# RubyWaves.net
KiCad netlist of a schematic drawn in EAGLE
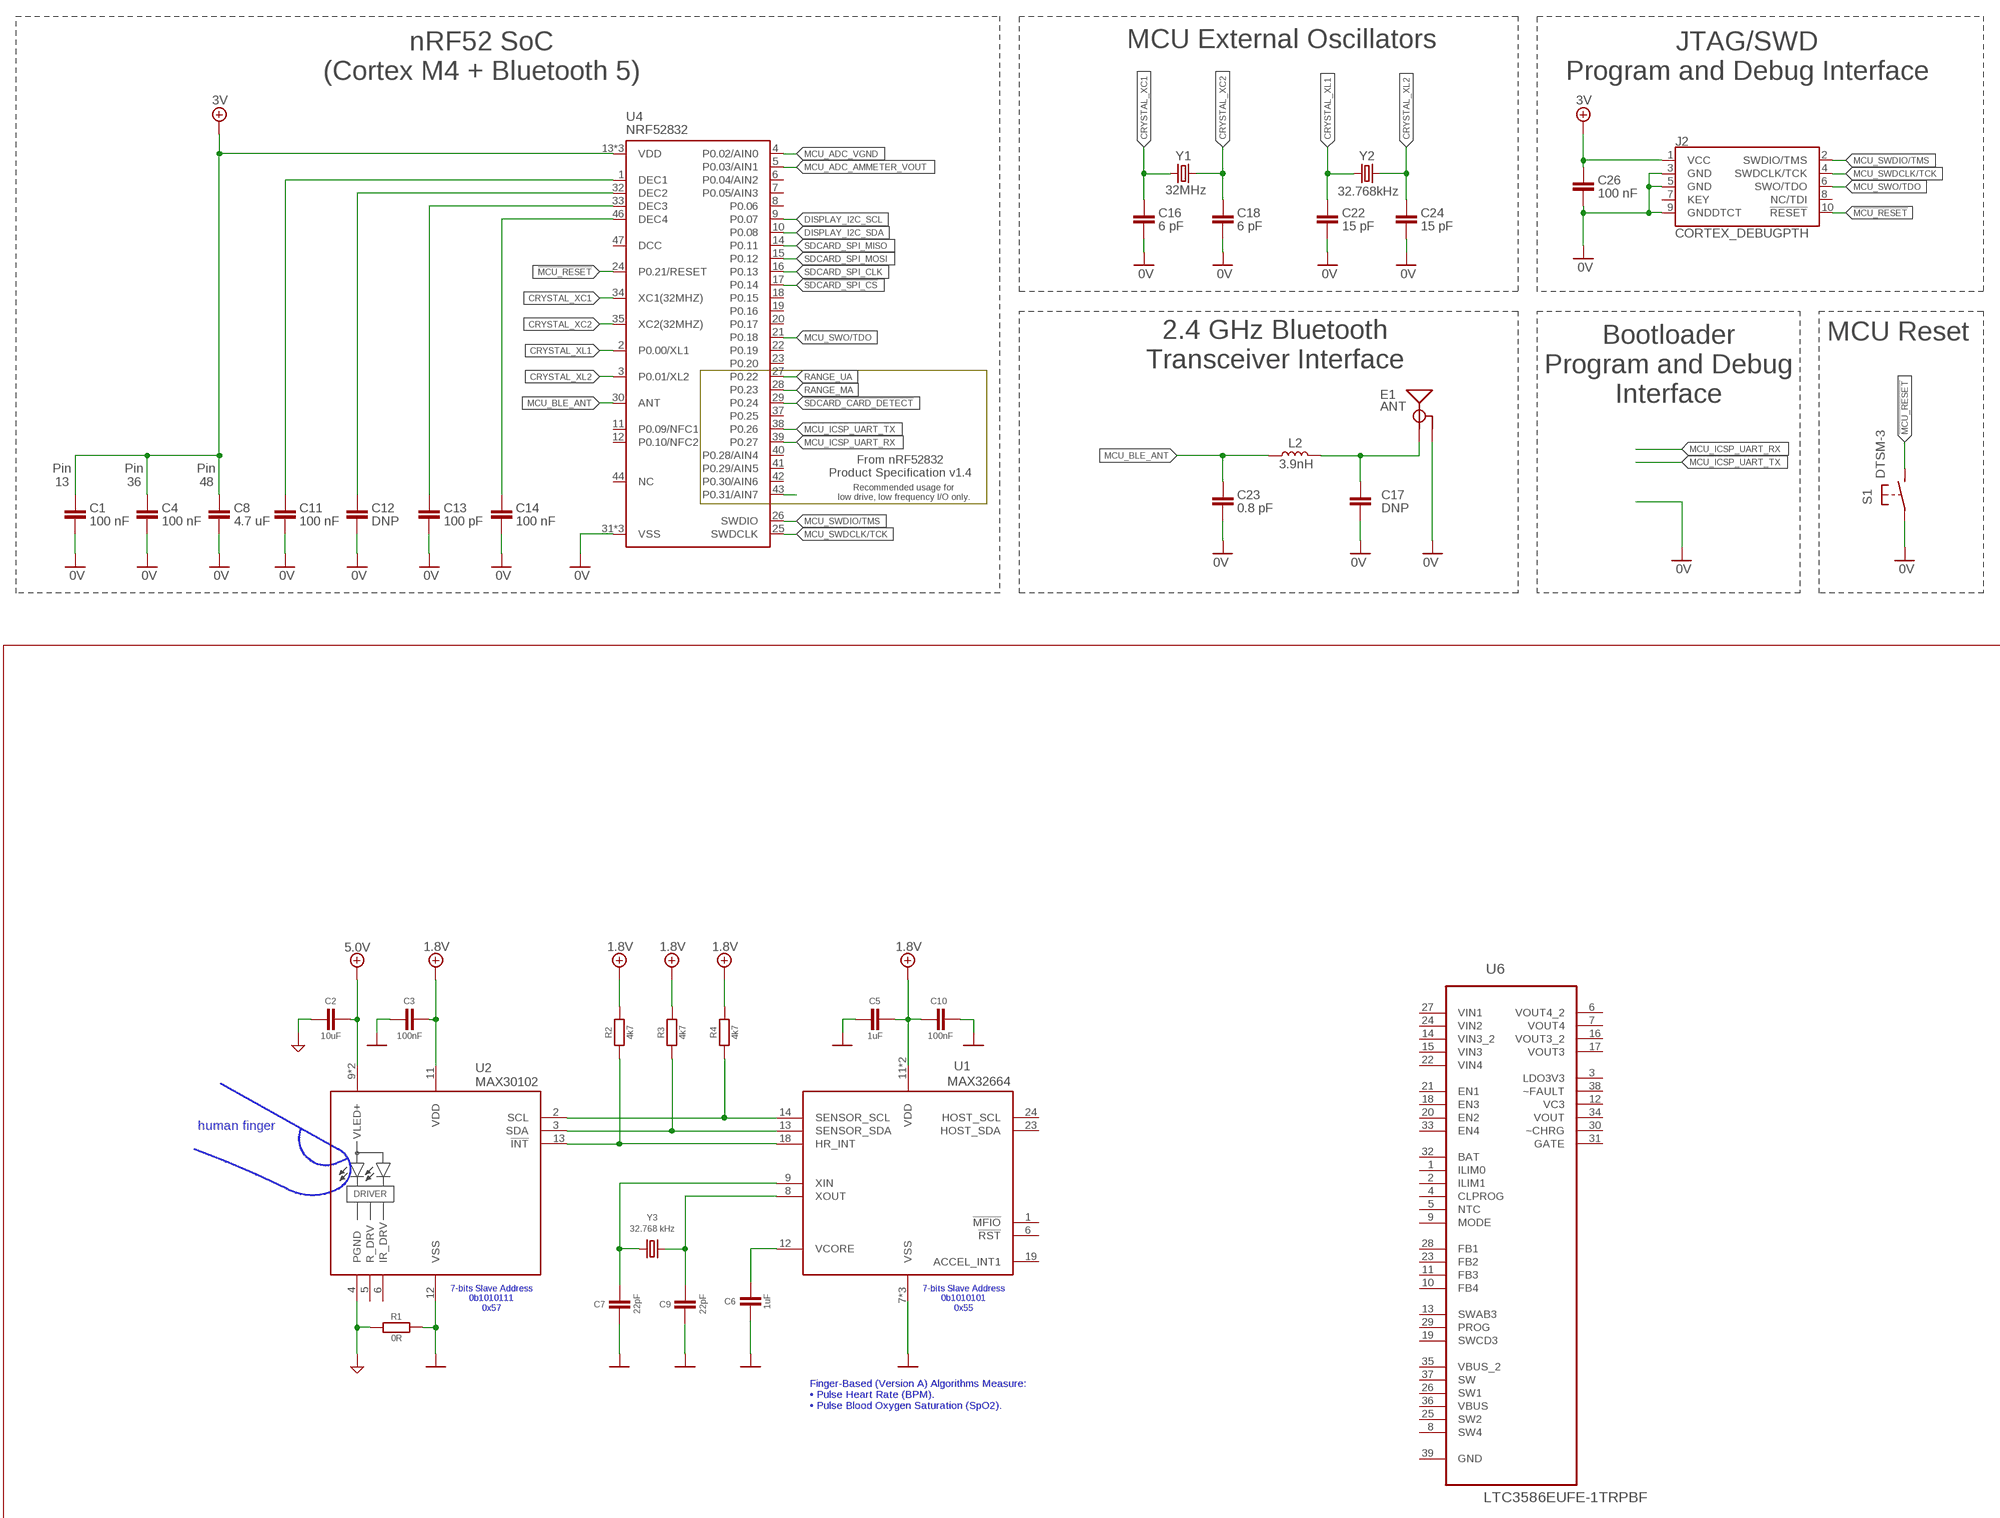
[diagram p0: schematic, sheet 1, part 1 of 2]
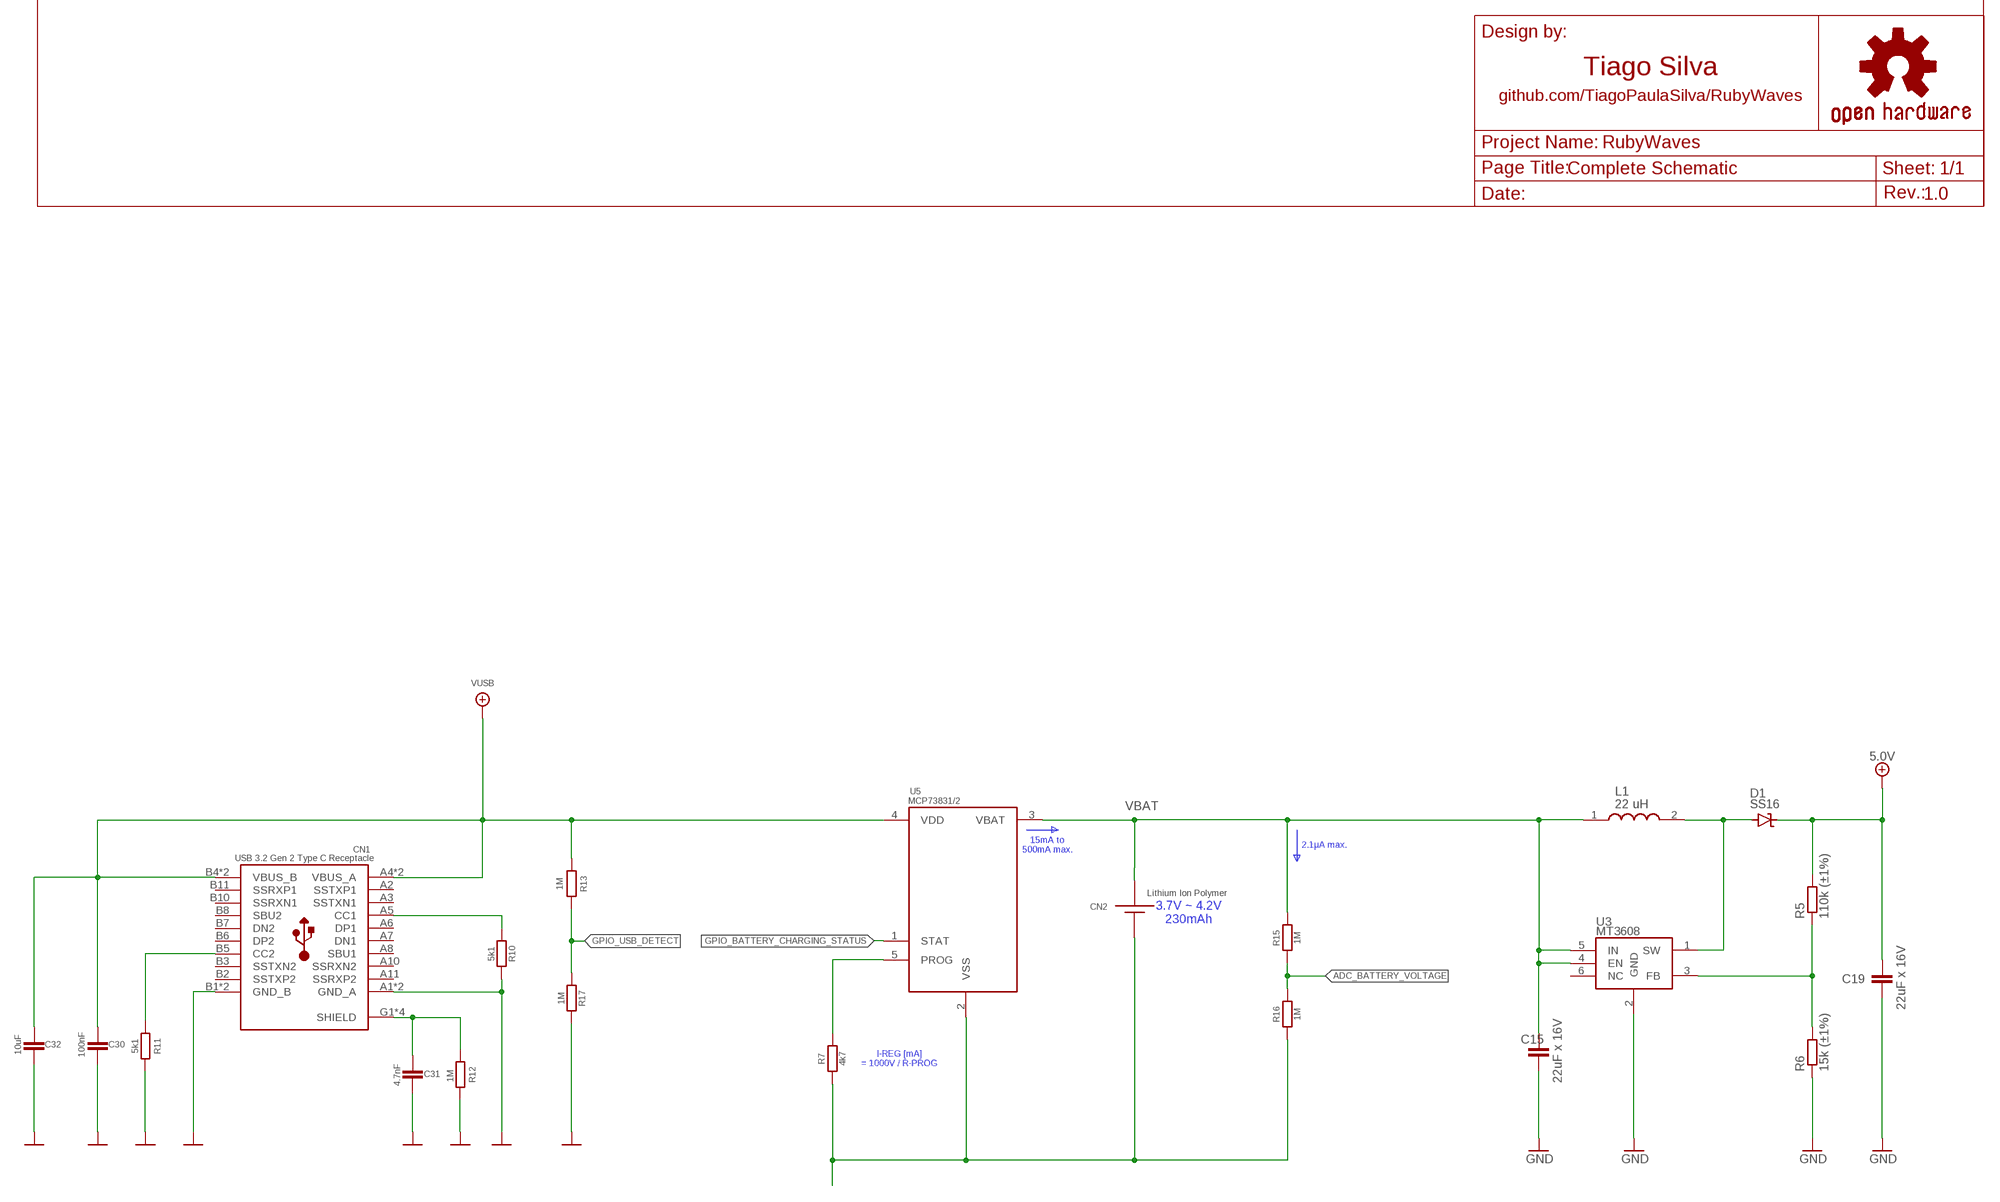
[diagram p1: schematic, sheet 1, part 2 of 2]

(export (version "E")
  (design (tool "Eeschema 10.0.6"))
  (components
    (comp (ref "C1")
      (value "100 nF")
      (footprint "eagle-import:C0603")
      (libsource (lib "eagle-import") (part "C-EUC0603"))
    )
    (comp (ref "C2")
      (value "10uF")
      (footprint "eagle-import:C0603")
      (libsource (lib "eagle-import") (part "C_0603"))
    )
    (comp (ref "C3")
      (value "100nF")
      (footprint "eagle-import:C0603")
      (libsource (lib "eagle-import") (part "C_0603"))
    )
    (comp (ref "C4")
      (value "100 nF")
      (footprint "eagle-import:C0603")
      (libsource (lib "eagle-import") (part "C-EUC0603"))
    )
    (comp (ref "C5")
      (value "1uF")
      (footprint "eagle-import:C0603")
      (libsource (lib "eagle-import") (part "C_0603"))
    )
    (comp (ref "C6")
      (value "1uF")
      (footprint "eagle-import:C0603")
      (libsource (lib "eagle-import") (part "C_0603"))
    )
    (comp (ref "C7")
      (value "22pF")
      (footprint "eagle-import:C0603")
      (libsource (lib "eagle-import") (part "C_0603"))
    )
    (comp (ref "C8")
      (value "4.7 uF")
      (footprint "eagle-import:C0603")
      (libsource (lib "eagle-import") (part "C-EUC0603"))
    )
    (comp (ref "C9")
      (value "22pF")
      (footprint "eagle-import:C0603")
      (libsource (lib "eagle-import") (part "C_0603"))
    )
    (comp (ref "C10")
      (value "100nF")
      (footprint "eagle-import:C0603")
      (libsource (lib "eagle-import") (part "C_0603"))
    )
    (comp (ref "C11")
      (value "100 nF")
      (footprint "eagle-import:C0603")
      (libsource (lib "eagle-import") (part "C-EUC0603"))
    )
    (comp (ref "C12")
      (value "DNP")
      (footprint "eagle-import:C0603")
      (libsource (lib "eagle-import") (part "C-EUC0603"))
    )
    (comp (ref "C13")
      (value "100 pF")
      (footprint "eagle-import:C0603")
      (libsource (lib "eagle-import") (part "C-EUC0603"))
    )
    (comp (ref "C14")
      (value "100 nF")
      (footprint "eagle-import:C0603")
      (libsource (lib "eagle-import") (part "C-EUC0603"))
    )
    (comp (ref "C15")
      (value "22uF x 16V")
      (footprint "eagle-import:C0805")
      (libsource (lib "eagle-import") (part "C-EUC0805"))
    )
    (comp (ref "C16")
      (value "6 pF")
      (footprint "eagle-import:C0603")
      (libsource (lib "eagle-import") (part "C-EUC0603"))
    )
    (comp (ref "C17")
      (value "DNP")
      (footprint "eagle-import:C0603")
      (libsource (lib "eagle-import") (part "C-EUC0603"))
    )
    (comp (ref "C18")
      (value "6 pF")
      (footprint "eagle-import:C0603")
      (libsource (lib "eagle-import") (part "C-EUC0603"))
    )
    (comp (ref "C19")
      (value "22uF x 16V")
      (footprint "eagle-import:C0805")
      (libsource (lib "eagle-import") (part "C-EUC0805"))
    )
    (comp (ref "C22")
      (value "15 pF")
      (footprint "eagle-import:C0603")
      (libsource (lib "eagle-import") (part "C-EUC0603"))
    )
    (comp (ref "C23")
      (value "0.8 pF")
      (footprint "eagle-import:C0603")
      (libsource (lib "eagle-import") (part "C-EUC0603"))
    )
    (comp (ref "C24")
      (value "15 pF")
      (footprint "eagle-import:C0603")
      (libsource (lib "eagle-import") (part "C-EUC0603"))
    )
    (comp (ref "C26")
      (value "100 nF")
      (footprint "eagle-import:C0603")
      (libsource (lib "eagle-import") (part "C-EUC0603"))
    )
    (comp (ref "C30")
      (value "100nF")
      (footprint "eagle-import:C0603")
      (libsource (lib "eagle-import") (part "C_0603"))
    )
    (comp (ref "C31")
      (value "4.7nF")
      (footprint "eagle-import:C0603")
      (libsource (lib "eagle-import") (part "C_0603"))
    )
    (comp (ref "C32")
      (value "10uF")
      (footprint "eagle-import:C0603")
      (libsource (lib "eagle-import") (part "C_0603"))
    )
    (comp (ref "CN1")
      (value "USB 3.2 Gen 2 Type C Receptacle")
      (footprint "eagle-import:GCT_USB4080-03-A_REVA")
      (fields (field (name "MF") "Global Connector Technology") (field (name "MP") "USB4080-03-A"))
      (libsource (lib "eagle-import") (part "USB4080-03-A"))
    )
    (comp (ref "CN2")
      (value "Lithium Ion Polymer")
      (footprint "eagle-import:JST-PH-2-SMT-RA")
      (libsource (lib "eagle-import") (part "BATTERYJST-2"))
    )
    (comp (ref "D1")
      (value "SS16")
      (footprint "eagle-import:SMBJ")
      (libsource (lib "eagle-import") (part "SUPPRESSOR-SMBJ"))
    )
    (comp (ref "E1")
      (value "ANT")
      (footprint "eagle-import:TRACE_ANTENNA_2.4GHZ_15.2MM")
      (libsource (lib "eagle-import") (part "ANTENNA-GROUNDEDTRACE-15.2MM"))
    )
    (comp (ref "J2")
      (value "CORTEX_DEBUGPTH")
      (footprint "eagle-import:2X5-PTH-1.27MM")
      (libsource (lib "eagle-import") (part "CORTEX_DEBUGPTH"))
    )
    (comp (ref "L1")
      (value "22 uH")
      (footprint "eagle-import:INDUCTOR")
      (libsource (lib "eagle-import") (part "INDUCTOR"))
    )
    (comp (ref "L2")
      (value "3.9nH")
      (footprint "eagle-import:0402")
      (libsource (lib "eagle-import") (part "INDUCTOR-0402-3.9NH"))
    )
    (comp (ref "R1")
      (value "0R")
      (footprint "eagle-import:R0603")
      (libsource (lib "eagle-import") (part "R_0603"))
    )
    (comp (ref "R2")
      (value "4k7")
      (footprint "eagle-import:R0603")
      (libsource (lib "eagle-import") (part "R_0603"))
    )
    (comp (ref "R3")
      (value "4k7")
      (footprint "eagle-import:R0603")
      (libsource (lib "eagle-import") (part "R_0603"))
    )
    (comp (ref "R4")
      (value "4k7")
      (footprint "eagle-import:R0603")
      (libsource (lib "eagle-import") (part "R_0603"))
    )
    (comp (ref "R5")
      (value "110k (±1%)")
      (footprint "eagle-import:R0603")
      (libsource (lib "eagle-import") (part "R-EU_R0603"))
    )
    (comp (ref "R6")
      (value "15k (±1%)")
      (footprint "eagle-import:R0603")
      (libsource (lib "eagle-import") (part "R-EU_R0603"))
    )
    (comp (ref "R7")
      (value "4k7")
      (footprint "eagle-import:R0603")
      (libsource (lib "eagle-import") (part "R_0603"))
    )
    (comp (ref "R10")
      (value "5k1")
      (footprint "eagle-import:R0603")
      (libsource (lib "eagle-import") (part "R_0603"))
    )
    (comp (ref "R11")
      (value "5k1")
      (footprint "eagle-import:R0603")
      (libsource (lib "eagle-import") (part "R_0603"))
    )
    (comp (ref "R12")
      (value "1M")
      (footprint "eagle-import:R0603")
      (libsource (lib "eagle-import") (part "R_0603"))
    )
    (comp (ref "R13")
      (value "1M")
      (footprint "eagle-import:R0603")
      (libsource (lib "eagle-import") (part "R_0603"))
    )
    (comp (ref "R15")
      (value "1M")
      (footprint "eagle-import:R0603")
      (libsource (lib "eagle-import") (part "R_0603"))
    )
    (comp (ref "R16")
      (value "1M")
      (footprint "eagle-import:R0603")
      (libsource (lib "eagle-import") (part "R_0603"))
    )
    (comp (ref "R17")
      (value "1M")
      (footprint "eagle-import:R0603")
      (libsource (lib "eagle-import") (part "R_0603"))
    )
    (comp (ref "S1")
      (value "DTSM-3")
      (footprint "eagle-import:SMD-2P")
      (libsource (lib "eagle-import") (part "DTSM-3"))
    )
    (comp (ref "U1")
      (value "MAX32664")
      (footprint "eagle-import:TQFN-24")
      (libsource (lib "eagle-import") (part "MAX32664"))
    )
    (comp (ref "U2")
      (value "MAX30102")
      (footprint "eagle-import:OESIP-14")
      (libsource (lib "eagle-import") (part "MAX30102"))
    )
    (comp (ref "U3")
      (value "MT3608")
      (footprint "eagle-import:SOT95P280X145-6N")
      (libsource (lib "eagle-import") (part "MT3608"))
    )
    (comp (ref "U4")
      (value "NRF52832")
      (footprint "eagle-import:QFN48-6X6MM")
      (libsource (lib "eagle-import") (part "NRF52832"))
    )
    (comp (ref "U5")
      (value "MCP73831/2")
      (footprint "eagle-import:SOT23-5L")
      (libsource (lib "eagle-import") (part "MCP73831/OT"))
    )
    (comp (ref "U6")
      (value "LTC3586EUFE-1TRPBF")
      (footprint "eagle-import:QFN40P400X600X80-39N")
      (fields (field (name "MF") "Analog Devices") (field (name "MP") "LTC3586EUFE-1#TRPBF"))
      (libsource (lib "eagle-import") (part "LTC3586EUFE-1TRPBF"))
    )
    (comp (ref "Y1")
      (value "32MHz")
      (footprint "eagle-import:CRYSTAL-SMD-2.0X1.6MM")
      (libsource (lib "eagle-import") (part "CRYSTAL-32MHZ-SMD-2.0X1.6MM"))
    )
    (comp (ref "Y2")
      (value "32.768kHz")
      (footprint "eagle-import:CRYSTAL-SMD-3.2X1.5MM")
      (libsource (lib "eagle-import") (part "CRYSTAL-32.768KHZSMD-3.2X1.5"))
    )
    (comp (ref "Y3")
      (value "32.768 kHz")
      (footprint "eagle-import:3.2X1.5")
      (libsource (lib "eagle-import") (part "CRYSTAL-MINI"))
    )
  )
  (nets
    (net (code "1") (name "/VBAT") (class "Default")
      (node (ref "C15") (pin "1") (pinfunction "1_1") (pintype "passive"))
      (node (ref "CN2") (pin "1") (pinfunction "VDD_1") (pintype "power_in"))
      (node (ref "L1") (pin "1") (pinfunction "1_1") (pintype "bidirectional"))
      (node (ref "R15") (pin "2") (pinfunction "2_2") (pintype "passive"))
      (node (ref "U3") (pin "4") (pinfunction "EN_4") (pintype "bidirectional"))
      (node (ref "U3") (pin "5") (pinfunction "IN_5") (pintype "bidirectional"))
      (node (ref "U5") (pin "3") (pinfunction "VBAT_3") (pintype "bidirectional"))
    )
    (net (code "2") (name "/VBUS") (class "Default")
      (node (ref "U6") (pin "36") (pinfunction "VBUS_36") (pintype "power_in"))
    )
    (net (code "3") (name "/VBUS_2") (class "Default")
      (node (ref "U6") (pin "35") (pinfunction "VBUS_2_35") (pintype "power_in"))
    )
    (net (code "4") (name "/VIN1") (class "Default")
      (node (ref "U6") (pin "27") (pinfunction "VIN1_27") (pintype "power_in"))
    )
    (net (code "5") (name "/VIN2") (class "Default")
      (node (ref "U6") (pin "24") (pinfunction "VIN2_24") (pintype "power_in"))
    )
    (net (code "6") (name "/VIN3") (class "Default")
      (node (ref "U6") (pin "15") (pinfunction "VIN3_15") (pintype "power_in"))
    )
    (net (code "7") (name "/VIN3_2") (class "Default")
      (node (ref "U6") (pin "14") (pinfunction "VIN3_2_14") (pintype "power_in"))
    )
    (net (code "8") (name "/VIN4") (class "Default")
      (node (ref "U6") (pin "22") (pinfunction "VIN4_22") (pintype "power_in"))
    )
    (net (code "9") (name "/~{MCU_RESET}") (class "Default")
      (node (ref "J2") (pin "10") (pinfunction "~{RESET}_10") (pintype "bidirectional"))
      (node (ref "S1") (pin "2") (pinfunction "2_2") (pintype "passive"))
      (node (ref "U4") (pin "24") (pinfunction "P0.21/RESET_24") (pintype "bidirectional"))
    )
    (net (code "10") (name "/~{SDCARD_CARD_DETECT}") (class "Default")
      (node (ref "U4") (pin "29") (pinfunction "P0.24_29") (pintype "bidirectional"))
    )
    (net (code "11") (name "/~{SDCARD_SPI_CS}") (class "Default")
      (node (ref "U4") (pin "17") (pinfunction "P0.14_17") (pintype "bidirectional"))
    )
    (net (code "12") (name "0V") (class "Default")
      (node (ref "C1") (pin "2") (pinfunction "2_2") (pintype "passive"))
      (node (ref "C11") (pin "2") (pinfunction "2_2") (pintype "passive"))
      (node (ref "C12") (pin "2") (pinfunction "2_2") (pintype "passive"))
      (node (ref "C13") (pin "2") (pinfunction "2_2") (pintype "passive"))
      (node (ref "C14") (pin "2") (pinfunction "2_2") (pintype "passive"))
      (node (ref "C16") (pin "2") (pinfunction "2_2") (pintype "passive"))
      (node (ref "C17") (pin "2") (pinfunction "2_2") (pintype "passive"))
      (node (ref "C18") (pin "2") (pinfunction "2_2") (pintype "passive"))
      (node (ref "C22") (pin "2") (pinfunction "2_2") (pintype "passive"))
      (node (ref "C23") (pin "2") (pinfunction "2_2") (pintype "passive"))
      (node (ref "C24") (pin "2") (pinfunction "2_2") (pintype "passive"))
      (node (ref "C26") (pin "2") (pinfunction "2_2") (pintype "passive"))
      (node (ref "C30") (pin "1") (pinfunction "1_1") (pintype "passive"))
      (node (ref "C31") (pin "1") (pinfunction "1_1") (pintype "passive"))
      (node (ref "C32") (pin "1") (pinfunction "1_1") (pintype "passive"))
      (node (ref "C4") (pin "2") (pinfunction "2_2") (pintype "passive"))
      (node (ref "C8") (pin "2") (pinfunction "2_2") (pintype "passive"))
      (node (ref "CN1") (pin "A1") (pinfunction "GND_A_A1") (pintype "power_in"))
      (node (ref "CN1") (pin "A12") (pinfunction "GND_A_A12") (pintype "power_in"))
      (node (ref "CN1") (pin "B1") (pinfunction "GND_B_B1") (pintype "power_in"))
      (node (ref "CN1") (pin "B12") (pinfunction "GND_B_B12") (pintype "power_in"))
      (node (ref "E1") (pin "GND") (pinfunction "GND_GND") (pintype "bidirectional"))
      (node (ref "J2") (pin "3") (pinfunction "GND_3") (pintype "bidirectional"))
      (node (ref "J2") (pin "5") (pinfunction "GND_5") (pintype "bidirectional"))
      (node (ref "J2") (pin "9") (pinfunction "GNDDTCT_9") (pintype "bidirectional"))
      (node (ref "R10") (pin "2") (pinfunction "2_2") (pintype "passive"))
      (node (ref "R11") (pin "2") (pinfunction "2_2") (pintype "passive"))
      (node (ref "R12") (pin "2") (pinfunction "2_2") (pintype "passive"))
      (node (ref "R17") (pin "1") (pinfunction "1_1") (pintype "passive"))
      (node (ref "S1") (pin "1") (pinfunction "1_1") (pintype "passive"))
      (node (ref "U4") (pin "31") (pinfunction "VSS_31") (pintype "bidirectional"))
      (node (ref "U4") (pin "45") (pinfunction "VSS_45") (pintype "bidirectional"))
      (node (ref "U4") (pin "EP") (pinfunction "VSS_EP") (pintype "bidirectional"))
    )
    (net (code "13") (name "1.8V") (class "Default")
      (node (ref "C10") (pin "1") (pinfunction "1_1") (pintype "passive"))
      (node (ref "C3") (pin "1") (pinfunction "1_1") (pintype "passive"))
      (node (ref "C5") (pin "1") (pinfunction "1_1") (pintype "passive"))
      (node (ref "R2") (pin "2") (pinfunction "2_2") (pintype "passive"))
      (node (ref "R3") (pin "2") (pinfunction "2_2") (pintype "passive"))
      (node (ref "R4") (pin "2") (pinfunction "2_2") (pintype "passive"))
      (node (ref "U1") (pin "11") (pinfunction "VDD_11") (pintype "bidirectional"))
      (node (ref "U1") (pin "22") (pinfunction "VDD_22") (pintype "bidirectional"))
      (node (ref "U2") (pin "11") (pinfunction "VDD_11") (pintype "power_in"))
    )
    (net (code "14") (name "3V") (class "Default")
      (node (ref "C1") (pin "1") (pinfunction "1_1") (pintype "passive"))
      (node (ref "C26") (pin "1") (pinfunction "1_1") (pintype "passive"))
      (node (ref "C4") (pin "1") (pinfunction "1_1") (pintype "passive"))
      (node (ref "C8") (pin "1") (pinfunction "1_1") (pintype "passive"))
      (node (ref "J2") (pin "1") (pinfunction "VCC_1") (pintype "bidirectional"))
      (node (ref "U4") (pin "13") (pinfunction "VDD_13") (pintype "bidirectional"))
      (node (ref "U4") (pin "36") (pinfunction "VDD_36") (pintype "bidirectional"))
      (node (ref "U4") (pin "48") (pinfunction "VDD_48") (pintype "bidirectional"))
    )
    (net (code "15") (name "5.0V") (class "Default")
      (node (ref "C19") (pin "1") (pinfunction "1_1") (pintype "passive"))
      (node (ref "C2") (pin "1") (pinfunction "1_1") (pintype "passive"))
      (node (ref "D1") (pin "C") (pinfunction "C_C") (pintype "passive"))
      (node (ref "R5") (pin "2") (pinfunction "2_2") (pintype "passive"))
      (node (ref "U2") (pin "10") (pinfunction "VLED+_10") (pintype "power_in"))
      (node (ref "U2") (pin "9") (pinfunction "VLED+_9") (pintype "power_in"))
    )
    (net (code "16") (name "ADC_BATTERY_VOLTAGE") (class "Default")
      (node (ref "R15") (pin "1") (pinfunction "1_1") (pintype "passive"))
      (node (ref "R16") (pin "2") (pinfunction "2_2") (pintype "passive"))
    )
    (net (code "17") (name "CRYSTAL_XC1") (class "Default")
      (node (ref "C16") (pin "1") (pinfunction "1_1") (pintype "passive"))
      (node (ref "U4") (pin "34") (pinfunction "XC1(32MHZ)_34") (pintype "bidirectional"))
      (node (ref "Y1") (pin "3") (pinfunction "2_3") (pintype "passive"))
    )
    (net (code "18") (name "CRYSTAL_XC2") (class "Default")
      (node (ref "C18") (pin "1") (pinfunction "1_1") (pintype "passive"))
      (node (ref "U4") (pin "35") (pinfunction "XC2(32MHZ)_35") (pintype "bidirectional"))
      (node (ref "Y1") (pin "1") (pinfunction "1_1") (pintype "passive"))
    )
    (net (code "19") (name "CRYSTAL_XL1") (class "Default")
      (node (ref "C22") (pin "1") (pinfunction "1_1") (pintype "passive"))
      (node (ref "U4") (pin "2") (pinfunction "P0.00/XL1_2") (pintype "bidirectional"))
      (node (ref "Y2") (pin "P$2") (pinfunction "2_P$2") (pintype "passive"))
    )
    (net (code "20") (name "CRYSTAL_XL2") (class "Default")
      (node (ref "C24") (pin "1") (pinfunction "1_1") (pintype "passive"))
      (node (ref "U4") (pin "3") (pinfunction "P0.01/XL2_3") (pintype "bidirectional"))
      (node (ref "Y2") (pin "P$1") (pinfunction "1_P$1") (pintype "passive"))
    )
    (net (code "21") (name "DGND") (class "Default")
      (node (ref "C2") (pin "2") (pinfunction "2_2") (pintype "passive"))
      (node (ref "R1") (pin "1") (pinfunction "1_1") (pintype "passive"))
      (node (ref "U2") (pin "4") (pinfunction "PGND_4") (pintype "power_in"))
    )
    (net (code "22") (name "DISPLAY_I2C_SCL") (class "Default")
      (node (ref "U4") (pin "9") (pinfunction "P0.07_9") (pintype "bidirectional"))
    )
    (net (code "23") (name "DISPLAY_I2C_SDA") (class "Default")
      (node (ref "U4") (pin "10") (pinfunction "P0.08_10") (pintype "bidirectional"))
    )
    (net (code "24") (name "GND") (class "Default")
      (node (ref "C15") (pin "2") (pinfunction "2_2") (pintype "passive"))
      (node (ref "C19") (pin "2") (pinfunction "2_2") (pintype "passive"))
      (node (ref "R6") (pin "1") (pinfunction "1_1") (pintype "passive"))
      (node (ref "U3") (pin "2") (pinfunction "GND_2") (pintype "bidirectional"))
    )
    (net (code "25") (name "GPIO_BATTERY_CHARGING_STATUS") (class "Default")
      (node (ref "U5") (pin "1") (pinfunction "STAT_1") (pintype "output"))
    )
    (net (code "26") (name "GPIO_USB_DETECT") (class "Default")
      (node (ref "R13") (pin "1") (pinfunction "1_1") (pintype "passive"))
      (node (ref "R17") (pin "2") (pinfunction "2_2") (pintype "passive"))
    )
    (net (code "27") (name "MCU_ADC_AMMETER_VOUT") (class "Default")
      (node (ref "U4") (pin "5") (pinfunction "P0.03/AIN1_5") (pintype "bidirectional"))
    )
    (net (code "28") (name "MCU_ADC_VGND") (class "Default")
      (node (ref "U4") (pin "4") (pinfunction "P0.02/AIN0_4") (pintype "bidirectional"))
    )
    (net (code "29") (name "MCU_BLE_ANT") (class "Default")
      (node (ref "C23") (pin "1") (pinfunction "1_1") (pintype "passive"))
      (node (ref "L2") (pin "2") (pinfunction "2_2") (pintype "passive"))
      (node (ref "U4") (pin "30") (pinfunction "ANT_30") (pintype "bidirectional"))
    )
    (net (code "30") (name "MCU_ICSP_UART_RX") (class "Default")
      (node (ref "U4") (pin "39") (pinfunction "P0.27_39") (pintype "bidirectional"))
    )
    (net (code "31") (name "MCU_ICSP_UART_TX") (class "Default")
      (node (ref "U4") (pin "38") (pinfunction "P0.26_38") (pintype "bidirectional"))
    )
    (net (code "32") (name "MCU_SWDCLK{slash}TCK") (class "Default")
      (node (ref "J2") (pin "4") (pinfunction "SWDCLK/TCK_4") (pintype "bidirectional"))
      (node (ref "U4") (pin "25") (pinfunction "SWDCLK_25") (pintype "bidirectional"))
    )
    (net (code "33") (name "MCU_SWDIO{slash}TMS") (class "Default")
      (node (ref "J2") (pin "2") (pinfunction "SWDIO/TMS_2") (pintype "bidirectional"))
      (node (ref "U4") (pin "26") (pinfunction "SWDIO_26") (pintype "bidirectional"))
    )
    (net (code "34") (name "MCU_SWO{slash}TDO") (class "Default")
      (node (ref "J2") (pin "6") (pinfunction "SWO/TDO_6") (pintype "bidirectional"))
      (node (ref "U4") (pin "21") (pinfunction "P0.18_21") (pintype "bidirectional"))
    )
    (net (code "35") (name "Net-(C31-Pad2)") (class "Default")
      (node (ref "C31") (pin "2") (pinfunction "2_2") (pintype "passive"))
      (node (ref "CN1") (pin "G1") (pinfunction "SHIELD_G1") (pintype "passive"))
      (node (ref "CN1") (pin "G2") (pinfunction "SHIELD_G2") (pintype "passive"))
      (node (ref "CN1") (pin "G3") (pinfunction "SHIELD_G3") (pintype "passive"))
      (node (ref "CN1") (pin "G4") (pinfunction "SHIELD_G4") (pintype "passive"))
      (node (ref "R12") (pin "1") (pinfunction "1_1") (pintype "passive"))
    )
    (net (code "36") (name "Net-(CN1-CC1)") (class "Default")
      (node (ref "CN1") (pin "A5") (pinfunction "CC1_A5") (pintype "bidirectional"))
      (node (ref "R10") (pin "1") (pinfunction "1_1") (pintype "passive"))
    )
    (net (code "37") (name "Net-(CN1-CC2)") (class "Default")
      (node (ref "CN1") (pin "B5") (pinfunction "CC2_B5") (pintype "bidirectional"))
      (node (ref "R11") (pin "1") (pinfunction "1_1") (pintype "passive"))
    )
    (net (code "38") (name "Net-(CN2-GND)") (class "Default")
      (node (ref "CN2") (pin "2") (pinfunction "GND_2") (pintype "power_in"))
      (node (ref "R16") (pin "1") (pinfunction "1_1") (pintype "passive"))
      (node (ref "R7") (pin "1") (pinfunction "1_1") (pintype "passive"))
      (node (ref "U5") (pin "2") (pinfunction "VSS_2") (pintype "power_in"))
    )
    (net (code "39") (name "Net-(E1-SIGNAL)") (class "Default")
      (node (ref "C17") (pin "1") (pinfunction "1_1") (pintype "passive"))
      (node (ref "E1") (pin "ANT") (pinfunction "SIGNAL_ANT") (pintype "bidirectional"))
      (node (ref "L2") (pin "1") (pinfunction "1_1") (pintype "passive"))
    )
    (net (code "40") (name "Net-(U1-HR_INT)") (class "Default")
      (node (ref "R2") (pin "1") (pinfunction "1_1") (pintype "passive"))
      (node (ref "U1") (pin "18") (pinfunction "HR_INT_18") (pintype "bidirectional"))
      (node (ref "U2") (pin "13") (pinfunction "~{INT}_13") (pintype "output"))
    )
    (net (code "41") (name "Net-(U1-SENSOR_SCL)") (class "Default")
      (node (ref "R4") (pin "1") (pinfunction "1_1") (pintype "passive"))
      (node (ref "U1") (pin "14") (pinfunction "SENSOR_SCL_14") (pintype "bidirectional"))
      (node (ref "U2") (pin "2") (pinfunction "SCL_2") (pintype "bidirectional"))
    )
    (net (code "42") (name "Net-(U1-SENSOR_SDA)") (class "Default")
      (node (ref "R3") (pin "1") (pinfunction "1_1") (pintype "passive"))
      (node (ref "U1") (pin "13") (pinfunction "SENSOR_SDA_13") (pintype "bidirectional"))
      (node (ref "U2") (pin "3") (pinfunction "SDA_3") (pintype "bidirectional"))
    )
    (net (code "43") (name "Net-(U1-VCORE)") (class "Default")
      (node (ref "C6") (pin "1") (pinfunction "1_1") (pintype "passive"))
      (node (ref "U1") (pin "12") (pinfunction "VCORE_12") (pintype "bidirectional"))
    )
    (net (code "44") (name "Net-(U1-XIN)") (class "Default")
      (node (ref "C7") (pin "1") (pinfunction "1_1") (pintype "passive"))
      (node (ref "U1") (pin "9") (pinfunction "XIN_9") (pintype "bidirectional"))
      (node (ref "Y3") (pin "1") (pinfunction "1_1") (pintype "passive"))
    )
    (net (code "45") (name "Net-(U1-XOUT)") (class "Default")
      (node (ref "C9") (pin "1") (pinfunction "1_1") (pintype "passive"))
      (node (ref "U1") (pin "8") (pinfunction "XOUT_8") (pintype "bidirectional"))
      (node (ref "Y3") (pin "2") (pinfunction "2_2") (pintype "passive"))
    )
    (net (code "46") (name "Net-(U3-FB)") (class "Default")
      (node (ref "R5") (pin "1") (pinfunction "1_1") (pintype "passive"))
      (node (ref "R6") (pin "2") (pinfunction "2_2") (pintype "passive"))
      (node (ref "U3") (pin "3") (pinfunction "FB_3") (pintype "bidirectional"))
    )
    (net (code "47") (name "Net-(U3-SW)") (class "Default")
      (node (ref "D1") (pin "A") (pinfunction "A_A") (pintype "passive"))
      (node (ref "L1") (pin "2") (pinfunction "2_2") (pintype "bidirectional"))
      (node (ref "U3") (pin "1") (pinfunction "SW_1") (pintype "bidirectional"))
    )
    (net (code "48") (name "Net-(U4-DEC1)") (class "Default")
      (node (ref "C11") (pin "1") (pinfunction "1_1") (pintype "passive"))
      (node (ref "U4") (pin "1") (pinfunction "DEC1_1") (pintype "bidirectional"))
    )
    (net (code "49") (name "Net-(U4-DEC2)") (class "Default")
      (node (ref "C12") (pin "1") (pinfunction "1_1") (pintype "passive"))
      (node (ref "U4") (pin "32") (pinfunction "DEC2_32") (pintype "bidirectional"))
    )
    (net (code "50") (name "Net-(U4-DEC3)") (class "Default")
      (node (ref "C13") (pin "1") (pinfunction "1_1") (pintype "passive"))
      (node (ref "U4") (pin "33") (pinfunction "DEC3_33") (pintype "bidirectional"))
    )
    (net (code "51") (name "Net-(U4-DEC4)") (class "Default")
      (node (ref "C14") (pin "1") (pinfunction "1_1") (pintype "passive"))
      (node (ref "U4") (pin "46") (pinfunction "DEC4_46") (pintype "bidirectional"))
    )
    (net (code "52") (name "Net-(U5-PROG)") (class "Default")
      (node (ref "R7") (pin "2") (pinfunction "2_2") (pintype "passive"))
      (node (ref "U5") (pin "5") (pinfunction "PROG_5") (pintype "input"))
    )
    (net (code "53") (name "RANGE_MA") (class "Default")
      (node (ref "U4") (pin "28") (pinfunction "P0.23_28") (pintype "bidirectional"))
    )
    (net (code "54") (name "RANGE_UA") (class "Default")
      (node (ref "U4") (pin "27") (pinfunction "P0.22_27") (pintype "bidirectional"))
    )
    (net (code "55") (name "SDCARD_SPI_CLK") (class "Default")
      (node (ref "U4") (pin "16") (pinfunction "P0.13_16") (pintype "bidirectional"))
    )
    (net (code "56") (name "SDCARD_SPI_MISO") (class "Default")
      (node (ref "U4") (pin "14") (pinfunction "P0.11_14") (pintype "bidirectional"))
    )
    (net (code "57") (name "SDCARD_SPI_MOSI") (class "Default")
      (node (ref "U4") (pin "15") (pinfunction "P0.12_15") (pintype "bidirectional"))
    )
    (net (code "58") (name "VSS") (class "Default")
      (node (ref "C10") (pin "2") (pinfunction "2_2") (pintype "passive"))
      (node (ref "C3") (pin "2") (pinfunction "2_2") (pintype "passive"))
      (node (ref "C5") (pin "2") (pinfunction "2_2") (pintype "passive"))
      (node (ref "C6") (pin "2") (pinfunction "2_2") (pintype "passive"))
      (node (ref "C7") (pin "2") (pinfunction "2_2") (pintype "passive"))
      (node (ref "C9") (pin "2") (pinfunction "2_2") (pintype "passive"))
      (node (ref "R1") (pin "2") (pinfunction "2_2") (pintype "passive"))
      (node (ref "U1") (pin "10") (pinfunction "VSS_10") (pintype "bidirectional"))
      (node (ref "U1") (pin "7") (pinfunction "VSS_7") (pintype "bidirectional"))
      (node (ref "U1") (pin "EP") (pinfunction "VSS_EP") (pintype "bidirectional"))
      (node (ref "U2") (pin "12") (pinfunction "VSS_12") (pintype "power_in"))
    )
    (net (code "59") (name "VUSB") (class "Default")
      (node (ref "C30") (pin "2") (pinfunction "2_2") (pintype "passive"))
      (node (ref "C32") (pin "2") (pinfunction "2_2") (pintype "passive"))
      (node (ref "CN1") (pin "A4") (pinfunction "VBUS_A_A4") (pintype "power_in"))
      (node (ref "CN1") (pin "A9") (pinfunction "VBUS_A_A9") (pintype "power_in"))
      (node (ref "CN1") (pin "B4") (pinfunction "VBUS_B_B4") (pintype "power_in"))
      (node (ref "CN1") (pin "B9") (pinfunction "VBUS_B_B9") (pintype "power_in"))
      (node (ref "R13") (pin "2") (pinfunction "2_2") (pintype "passive"))
      (node (ref "U5") (pin "4") (pinfunction "VDD_4") (pintype "power_in"))
    )
    (net (code "60") (name "unconnected-(CN1-DN1-PadA7)") (class "Default")
      (node (ref "CN1") (pin "A7") (pinfunction "DN1_A7") (pintype "bidirectional"))
    )
    (net (code "61") (name "unconnected-(CN1-DN2-PadB7)") (class "Default")
      (node (ref "CN1") (pin "B7") (pinfunction "DN2_B7") (pintype "bidirectional"))
    )
    (net (code "62") (name "unconnected-(CN1-DP1-PadA6)") (class "Default")
      (node (ref "CN1") (pin "A6") (pinfunction "DP1_A6") (pintype "bidirectional"))
    )
    (net (code "63") (name "unconnected-(CN1-DP2-PadB6)") (class "Default")
      (node (ref "CN1") (pin "B6") (pinfunction "DP2_B6") (pintype "bidirectional"))
    )
    (net (code "64") (name "unconnected-(CN1-SBU1-PadA8)") (class "Default")
      (node (ref "CN1") (pin "A8") (pinfunction "SBU1_A8") (pintype "bidirectional"))
    )
    (net (code "65") (name "unconnected-(CN1-SBU2-PadB8)") (class "Default")
      (node (ref "CN1") (pin "B8") (pinfunction "SBU2_B8") (pintype "bidirectional"))
    )
    (net (code "66") (name "unconnected-(CN1-SSRXN1-PadB10)") (class "Default")
      (node (ref "CN1") (pin "B10") (pinfunction "SSRXN1_B10") (pintype "bidirectional"))
    )
    (net (code "67") (name "unconnected-(CN1-SSRXN2-PadA10)") (class "Default")
      (node (ref "CN1") (pin "A10") (pinfunction "SSRXN2_A10") (pintype "bidirectional"))
    )
    (net (code "68") (name "unconnected-(CN1-SSRXP1-PadB11)") (class "Default")
      (node (ref "CN1") (pin "B11") (pinfunction "SSRXP1_B11") (pintype "bidirectional"))
    )
    (net (code "69") (name "unconnected-(CN1-SSRXP2-PadA11)") (class "Default")
      (node (ref "CN1") (pin "A11") (pinfunction "SSRXP2_A11") (pintype "bidirectional"))
    )
    (net (code "70") (name "unconnected-(CN1-SSTXN1-PadA3)") (class "Default")
      (node (ref "CN1") (pin "A3") (pinfunction "SSTXN1_A3") (pintype "bidirectional"))
    )
    (net (code "71") (name "unconnected-(CN1-SSTXN2-PadB3)") (class "Default")
      (node (ref "CN1") (pin "B3") (pinfunction "SSTXN2_B3") (pintype "bidirectional"))
    )
    (net (code "72") (name "unconnected-(CN1-SSTXP1-PadA2)") (class "Default")
      (node (ref "CN1") (pin "A2") (pinfunction "SSTXP1_A2") (pintype "bidirectional"))
    )
    (net (code "73") (name "unconnected-(CN1-SSTXP2-PadB2)") (class "Default")
      (node (ref "CN1") (pin "B2") (pinfunction "SSTXP2_B2") (pintype "bidirectional"))
    )
    (net (code "74") (name "unconnected-(J2-KEY-Pad7)") (class "Default")
      (node (ref "J2") (pin "7") (pinfunction "KEY_7") (pintype "bidirectional"))
    )
    (net (code "75") (name "unconnected-(J2-NC{slash}TDI-Pad8)") (class "Default")
      (node (ref "J2") (pin "8") (pinfunction "NC/TDI_8") (pintype "bidirectional"))
    )
    (net (code "76") (name "unconnected-(U1-ACCEL_INT1-Pad19)") (class "Default")
      (node (ref "U1") (pin "19") (pinfunction "ACCEL_INT1_19") (pintype "bidirectional"))
    )
    (net (code "77") (name "unconnected-(U1-HOST_SCL-Pad24)") (class "Default")
      (node (ref "U1") (pin "24") (pinfunction "HOST_SCL_24") (pintype "bidirectional"))
    )
    (net (code "78") (name "unconnected-(U1-HOST_SDA-Pad23)") (class "Default")
      (node (ref "U1") (pin "23") (pinfunction "HOST_SDA_23") (pintype "bidirectional"))
    )
    (net (code "79") (name "unconnected-(U1-~{MFIO}-Pad1)") (class "Default")
      (node (ref "U1") (pin "1") (pinfunction "~{MFIO}_1") (pintype "bidirectional"))
    )
    (net (code "80") (name "unconnected-(U1-~{RST}-Pad6)") (class "Default")
      (node (ref "U1") (pin "6") (pinfunction "~{RST}_6") (pintype "bidirectional"))
    )
    (net (code "81") (name "unconnected-(U2-IR_DRV-Pad6)") (class "Default")
      (node (ref "U2") (pin "6") (pinfunction "IR_DRV_6") (pintype "no_connect"))
    )
    (net (code "82") (name "unconnected-(U2-R_DRV-Pad5)") (class "Default")
      (node (ref "U2") (pin "5") (pinfunction "R_DRV_5") (pintype "no_connect"))
    )
    (net (code "83") (name "unconnected-(U3-NC-Pad6)") (class "Default")
      (node (ref "U3") (pin "6") (pinfunction "NC_6") (pintype "no_connect"))
    )
    (net (code "84") (name "unconnected-(U4-DCC-Pad47)") (class "Default")
      (node (ref "U4") (pin "47") (pinfunction "DCC_47") (pintype "bidirectional"))
    )
    (net (code "85") (name "unconnected-(U4-NC-Pad44)") (class "Default")
      (node (ref "U4") (pin "44") (pinfunction "NC_44") (pintype "bidirectional"))
    )
    (net (code "86") (name "unconnected-(U4-P0.04{slash}AIN2-Pad6)") (class "Default")
      (node (ref "U4") (pin "6") (pinfunction "P0.04/AIN2_6") (pintype "bidirectional"))
    )
    (net (code "87") (name "unconnected-(U4-P0.05{slash}AIN3-Pad7)") (class "Default")
      (node (ref "U4") (pin "7") (pinfunction "P0.05/AIN3_7") (pintype "bidirectional"))
    )
    (net (code "88") (name "unconnected-(U4-P0.06-Pad8)") (class "Default")
      (node (ref "U4") (pin "8") (pinfunction "P0.06_8") (pintype "bidirectional"))
    )
    (net (code "89") (name "unconnected-(U4-P0.09{slash}NFC1-Pad11)") (class "Default")
      (node (ref "U4") (pin "11") (pinfunction "P0.09/NFC1_11") (pintype "bidirectional"))
    )
    (net (code "90") (name "unconnected-(U4-P0.10{slash}NFC2-Pad12)") (class "Default")
      (node (ref "U4") (pin "12") (pinfunction "P0.10/NFC2_12") (pintype "bidirectional"))
    )
    (net (code "91") (name "unconnected-(U4-P0.15-Pad18)") (class "Default")
      (node (ref "U4") (pin "18") (pinfunction "P0.15_18") (pintype "bidirectional"))
    )
    (net (code "92") (name "unconnected-(U4-P0.16-Pad19)") (class "Default")
      (node (ref "U4") (pin "19") (pinfunction "P0.16_19") (pintype "bidirectional"))
    )
    (net (code "93") (name "unconnected-(U4-P0.17-Pad20)") (class "Default")
      (node (ref "U4") (pin "20") (pinfunction "P0.17_20") (pintype "bidirectional"))
    )
    (net (code "94") (name "unconnected-(U4-P0.19-Pad22)") (class "Default")
      (node (ref "U4") (pin "22") (pinfunction "P0.19_22") (pintype "bidirectional"))
    )
    (net (code "95") (name "unconnected-(U4-P0.20-Pad23)") (class "Default")
      (node (ref "U4") (pin "23") (pinfunction "P0.20_23") (pintype "bidirectional"))
    )
    (net (code "96") (name "unconnected-(U4-P0.25-Pad37)") (class "Default")
      (node (ref "U4") (pin "37") (pinfunction "P0.25_37") (pintype "bidirectional"))
    )
    (net (code "97") (name "unconnected-(U4-P0.28{slash}AIN4-Pad40)") (class "Default")
      (node (ref "U4") (pin "40") (pinfunction "P0.28/AIN4_40") (pintype "bidirectional"))
    )
    (net (code "98") (name "unconnected-(U4-P0.29{slash}AIN5-Pad41)") (class "Default")
      (node (ref "U4") (pin "41") (pinfunction "P0.29/AIN5_41") (pintype "bidirectional"))
    )
    (net (code "99") (name "unconnected-(U4-P0.30{slash}AIN6-Pad42)") (class "Default")
      (node (ref "U4") (pin "42") (pinfunction "P0.30/AIN6_42") (pintype "bidirectional"))
    )
    (net (code "100") (name "unconnected-(U4-P0.31{slash}AIN7-Pad43)") (class "Default")
      (node (ref "U4") (pin "43") (pinfunction "P0.31/AIN7_43") (pintype "bidirectional"))
    )
    (net (code "101") (name "unconnected-(U6-BAT-Pad32)") (class "Default")
      (node (ref "U6") (pin "32") (pinfunction "BAT_32") (pintype "input"))
    )
    (net (code "102") (name "unconnected-(U6-CLPROG-Pad4)") (class "Default")
      (node (ref "U6") (pin "4") (pinfunction "CLPROG_4") (pintype "input"))
    )
    (net (code "103") (name "unconnected-(U6-EN1-Pad21)") (class "Default")
      (node (ref "U6") (pin "21") (pinfunction "EN1_21") (pintype "input"))
    )
    (net (code "104") (name "unconnected-(U6-EN2-Pad20)") (class "Default")
      (node (ref "U6") (pin "20") (pinfunction "EN2_20") (pintype "input"))
    )
    (net (code "105") (name "unconnected-(U6-EN3-Pad18)") (class "Default")
      (node (ref "U6") (pin "18") (pinfunction "EN3_18") (pintype "input"))
    )
    (net (code "106") (name "unconnected-(U6-EN4-Pad33)") (class "Default")
      (node (ref "U6") (pin "33") (pinfunction "EN4_33") (pintype "input"))
    )
    (net (code "107") (name "unconnected-(U6-FB1-Pad28)") (class "Default")
      (node (ref "U6") (pin "28") (pinfunction "FB1_28") (pintype "input"))
    )
    (net (code "108") (name "unconnected-(U6-FB2-Pad23)") (class "Default")
      (node (ref "U6") (pin "23") (pinfunction "FB2_23") (pintype "input"))
    )
    (net (code "109") (name "unconnected-(U6-FB3-Pad11)") (class "Default")
      (node (ref "U6") (pin "11") (pinfunction "FB3_11") (pintype "input"))
    )
    (net (code "110") (name "unconnected-(U6-FB4-Pad10)") (class "Default")
      (node (ref "U6") (pin "10") (pinfunction "FB4_10") (pintype "input"))
    )
    (net (code "111") (name "unconnected-(U6-GATE-Pad31)") (class "Default")
      (node (ref "U6") (pin "31") (pinfunction "GATE_31") (pintype "output"))
    )
    (net (code "112") (name "unconnected-(U6-GND-Pad39)") (class "Default")
      (node (ref "U6") (pin "39") (pinfunction "GND_39") (pintype "passive"))
    )
    (net (code "113") (name "unconnected-(U6-ILIM0-Pad1)") (class "Default")
      (node (ref "U6") (pin "1") (pinfunction "ILIM0_1") (pintype "input"))
    )
    (net (code "114") (name "unconnected-(U6-ILIM1-Pad2)") (class "Default")
      (node (ref "U6") (pin "2") (pinfunction "ILIM1_2") (pintype "input"))
    )
    (net (code "115") (name "unconnected-(U6-LDO3V3-Pad3)") (class "Default")
      (node (ref "U6") (pin "3") (pinfunction "LDO3V3_3") (pintype "output"))
    )
    (net (code "116") (name "unconnected-(U6-MODE-Pad9)") (class "Default")
      (node (ref "U6") (pin "9") (pinfunction "MODE_9") (pintype "input"))
    )
    (net (code "117") (name "unconnected-(U6-NTC-Pad5)") (class "Default")
      (node (ref "U6") (pin "5") (pinfunction "NTC_5") (pintype "input"))
    )
    (net (code "118") (name "unconnected-(U6-PROG-Pad29)") (class "Default")
      (node (ref "U6") (pin "29") (pinfunction "PROG_29") (pintype "input"))
    )
    (net (code "119") (name "unconnected-(U6-SW-Pad37)") (class "Default")
      (node (ref "U6") (pin "37") (pinfunction "SW_37") (pintype "input"))
    )
    (net (code "120") (name "unconnected-(U6-SW1-Pad26)") (class "Default")
      (node (ref "U6") (pin "26") (pinfunction "SW1_26") (pintype "input"))
    )
    (net (code "121") (name "unconnected-(U6-SW2-Pad25)") (class "Default")
      (node (ref "U6") (pin "25") (pinfunction "SW2_25") (pintype "input"))
    )
    (net (code "122") (name "unconnected-(U6-SW4-Pad8)") (class "Default")
      (node (ref "U6") (pin "8") (pinfunction "SW4_8") (pintype "input"))
    )
    (net (code "123") (name "unconnected-(U6-SWAB3-Pad13)") (class "Default")
      (node (ref "U6") (pin "13") (pinfunction "SWAB3_13") (pintype "output"))
    )
    (net (code "124") (name "unconnected-(U6-SWCD3-Pad19)") (class "Default")
      (node (ref "U6") (pin "19") (pinfunction "SWCD3_19") (pintype "input"))
    )
    (net (code "125") (name "unconnected-(U6-VC3-Pad12)") (class "Default")
      (node (ref "U6") (pin "12") (pinfunction "VC3_12") (pintype "output"))
    )
    (net (code "126") (name "unconnected-(U6-VOUT-Pad34)") (class "Default")
      (node (ref "U6") (pin "34") (pinfunction "VOUT_34") (pintype "output"))
    )
    (net (code "127") (name "unconnected-(U6-VOUT3-Pad17)") (class "Default")
      (node (ref "U6") (pin "17") (pinfunction "VOUT3_17") (pintype "output"))
    )
    (net (code "128") (name "unconnected-(U6-VOUT3_2-Pad16)") (class "Default")
      (node (ref "U6") (pin "16") (pinfunction "VOUT3_2_16") (pintype "output"))
    )
    (net (code "129") (name "unconnected-(U6-VOUT4-Pad7)") (class "Default")
      (node (ref "U6") (pin "7") (pinfunction "VOUT4_7") (pintype "output"))
    )
    (net (code "130") (name "unconnected-(U6-VOUT4_2-Pad6)") (class "Default")
      (node (ref "U6") (pin "6") (pinfunction "VOUT4_2_6") (pintype "output"))
    )
    (net (code "131") (name "unconnected-(U6-~{CHRG}-Pad30)") (class "Default")
      (node (ref "U6") (pin "30") (pinfunction "~{CHRG}_30") (pintype "output"))
    )
    (net (code "132") (name "unconnected-(U6-~{FAULT}-Pad38)") (class "Default")
      (node (ref "U6") (pin "38") (pinfunction "~{FAULT}_38") (pintype "output"))
    )
  )
)
